# Lampara.net
KiCad netlist of a schematic drawn in EAGLE
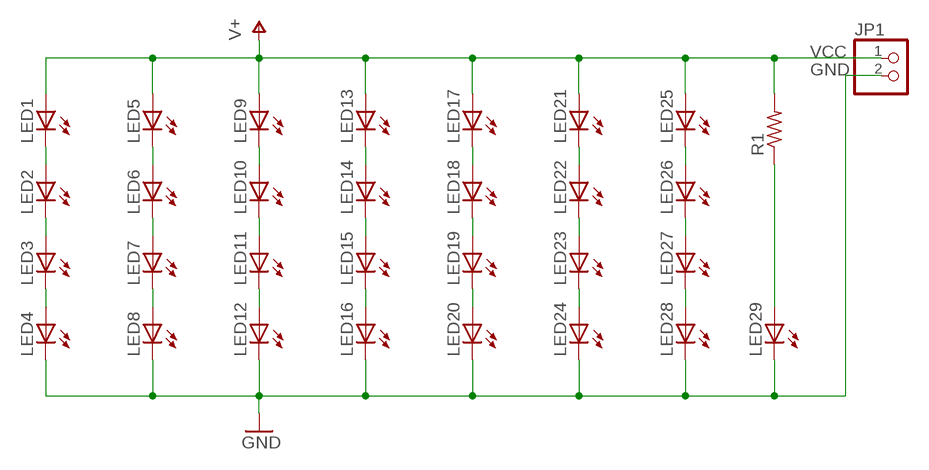
[diagram p0: schematic, sheet 1]

(export (version "E")
  (design (tool "Eeschema 10.0.6"))
  (components
    (comp (ref "JP1")
      (value "PINHD-1X2/90")
      (footprint "eagle-import:1X02_90")
      (libsource (lib "eagle-import") (part "PINHD-1X2/90"))
    )
    (comp (ref "LED1")
      (value "LED5MM")
      (footprint "eagle-import:LED5MM")
      (libsource (lib "eagle-import") (part "LED5MM"))
    )
    (comp (ref "LED2")
      (value "LED5MM")
      (footprint "eagle-import:LED5MM")
      (libsource (lib "eagle-import") (part "LED5MM"))
    )
    (comp (ref "LED3")
      (value "LED5MM")
      (footprint "eagle-import:LED5MM")
      (libsource (lib "eagle-import") (part "LED5MM"))
    )
    (comp (ref "LED4")
      (value "LED5MM")
      (footprint "eagle-import:LED5MM")
      (libsource (lib "eagle-import") (part "LED5MM"))
    )
    (comp (ref "LED5")
      (value "LED5MM")
      (footprint "eagle-import:LED5MM")
      (libsource (lib "eagle-import") (part "LED5MM"))
    )
    (comp (ref "LED6")
      (value "LED5MM")
      (footprint "eagle-import:LED5MM")
      (libsource (lib "eagle-import") (part "LED5MM"))
    )
    (comp (ref "LED7")
      (value "LED5MM")
      (footprint "eagle-import:LED5MM")
      (libsource (lib "eagle-import") (part "LED5MM"))
    )
    (comp (ref "LED8")
      (value "LED5MM")
      (footprint "eagle-import:LED5MM")
      (libsource (lib "eagle-import") (part "LED5MM"))
    )
    (comp (ref "LED9")
      (value "LED5MM")
      (footprint "eagle-import:LED5MM")
      (libsource (lib "eagle-import") (part "LED5MM"))
    )
    (comp (ref "LED10")
      (value "LED5MM")
      (footprint "eagle-import:LED5MM")
      (libsource (lib "eagle-import") (part "LED5MM"))
    )
    (comp (ref "LED11")
      (value "LED5MM")
      (footprint "eagle-import:LED5MM")
      (libsource (lib "eagle-import") (part "LED5MM"))
    )
    (comp (ref "LED12")
      (value "LED5MM")
      (footprint "eagle-import:LED5MM")
      (libsource (lib "eagle-import") (part "LED5MM"))
    )
    (comp (ref "LED13")
      (value "LED5MM")
      (footprint "eagle-import:LED5MM")
      (libsource (lib "eagle-import") (part "LED5MM"))
    )
    (comp (ref "LED14")
      (value "LED5MM")
      (footprint "eagle-import:LED5MM")
      (libsource (lib "eagle-import") (part "LED5MM"))
    )
    (comp (ref "LED15")
      (value "LED5MM")
      (footprint "eagle-import:LED5MM")
      (libsource (lib "eagle-import") (part "LED5MM"))
    )
    (comp (ref "LED16")
      (value "LED5MM")
      (footprint "eagle-import:LED5MM")
      (libsource (lib "eagle-import") (part "LED5MM"))
    )
    (comp (ref "LED17")
      (value "LED5MM")
      (footprint "eagle-import:LED5MM")
      (libsource (lib "eagle-import") (part "LED5MM"))
    )
    (comp (ref "LED18")
      (value "LED5MM")
      (footprint "eagle-import:LED5MM")
      (libsource (lib "eagle-import") (part "LED5MM"))
    )
    (comp (ref "LED19")
      (value "LED5MM")
      (footprint "eagle-import:LED5MM")
      (libsource (lib "eagle-import") (part "LED5MM"))
    )
    (comp (ref "LED20")
      (value "LED5MM")
      (footprint "eagle-import:LED5MM")
      (libsource (lib "eagle-import") (part "LED5MM"))
    )
    (comp (ref "LED21")
      (value "LED5MM")
      (footprint "eagle-import:LED5MM")
      (libsource (lib "eagle-import") (part "LED5MM"))
    )
    (comp (ref "LED22")
      (value "LED5MM")
      (footprint "eagle-import:LED5MM")
      (libsource (lib "eagle-import") (part "LED5MM"))
    )
    (comp (ref "LED23")
      (value "LED5MM")
      (footprint "eagle-import:LED5MM")
      (libsource (lib "eagle-import") (part "LED5MM"))
    )
    (comp (ref "LED24")
      (value "LED5MM")
      (footprint "eagle-import:LED5MM")
      (libsource (lib "eagle-import") (part "LED5MM"))
    )
    (comp (ref "LED25")
      (value "LED5MM")
      (footprint "eagle-import:LED5MM")
      (libsource (lib "eagle-import") (part "LED5MM"))
    )
    (comp (ref "LED26")
      (value "LED5MM")
      (footprint "eagle-import:LED5MM")
      (libsource (lib "eagle-import") (part "LED5MM"))
    )
    (comp (ref "LED27")
      (value "LED5MM")
      (footprint "eagle-import:LED5MM")
      (libsource (lib "eagle-import") (part "LED5MM"))
    )
    (comp (ref "LED28")
      (value "LED5MM")
      (footprint "eagle-import:LED5MM")
      (libsource (lib "eagle-import") (part "LED5MM"))
    )
    (comp (ref "LED29")
      (value "LED5MM")
      (footprint "eagle-import:LED5MM")
      (libsource (lib "eagle-import") (part "LED5MM"))
    )
    (comp (ref "R1")
      (value "R-US_0204/7")
      (footprint "eagle-import:0204_7")
      (libsource (lib "eagle-import") (part "R-US_0204/7"))
    )
  )
  (nets
    (net (code "1") (name "GND") (class "Default")
      (node (ref "JP1") (pin "2") (pinfunction "2_2") (pintype "passive"))
      (node (ref "LED12") (pin "K") (pinfunction "C_K") (pintype "passive"))
      (node (ref "LED16") (pin "K") (pinfunction "C_K") (pintype "passive"))
      (node (ref "LED20") (pin "K") (pinfunction "C_K") (pintype "passive"))
      (node (ref "LED24") (pin "K") (pinfunction "C_K") (pintype "passive"))
      (node (ref "LED28") (pin "K") (pinfunction "C_K") (pintype "passive"))
      (node (ref "LED29") (pin "K") (pinfunction "C_K") (pintype "passive"))
      (node (ref "LED4") (pin "K") (pinfunction "C_K") (pintype "passive"))
      (node (ref "LED8") (pin "K") (pinfunction "C_K") (pintype "passive"))
    )
    (net (code "2") (name "Net-(LED1-C)") (class "Default")
      (node (ref "LED1") (pin "K") (pinfunction "C_K") (pintype "passive"))
      (node (ref "LED2") (pin "A") (pinfunction "A_A") (pintype "passive"))
    )
    (net (code "3") (name "Net-(LED2-C)") (class "Default")
      (node (ref "LED2") (pin "K") (pinfunction "C_K") (pintype "passive"))
      (node (ref "LED3") (pin "A") (pinfunction "A_A") (pintype "passive"))
    )
    (net (code "4") (name "Net-(LED3-C)") (class "Default")
      (node (ref "LED3") (pin "K") (pinfunction "C_K") (pintype "passive"))
      (node (ref "LED4") (pin "A") (pinfunction "A_A") (pintype "passive"))
    )
    (net (code "5") (name "Net-(LED5-C)") (class "Default")
      (node (ref "LED5") (pin "K") (pinfunction "C_K") (pintype "passive"))
      (node (ref "LED6") (pin "A") (pinfunction "A_A") (pintype "passive"))
    )
    (net (code "6") (name "Net-(LED6-C)") (class "Default")
      (node (ref "LED6") (pin "K") (pinfunction "C_K") (pintype "passive"))
      (node (ref "LED7") (pin "A") (pinfunction "A_A") (pintype "passive"))
    )
    (net (code "7") (name "Net-(LED7-C)") (class "Default")
      (node (ref "LED7") (pin "K") (pinfunction "C_K") (pintype "passive"))
      (node (ref "LED8") (pin "A") (pinfunction "A_A") (pintype "passive"))
    )
    (net (code "8") (name "Net-(LED9-C)") (class "Default")
      (node (ref "LED10") (pin "A") (pinfunction "A_A") (pintype "passive"))
      (node (ref "LED9") (pin "K") (pinfunction "C_K") (pintype "passive"))
    )
    (net (code "9") (name "Net-(LED10-C)") (class "Default")
      (node (ref "LED10") (pin "K") (pinfunction "C_K") (pintype "passive"))
      (node (ref "LED11") (pin "A") (pinfunction "A_A") (pintype "passive"))
    )
    (net (code "10") (name "Net-(LED11-C)") (class "Default")
      (node (ref "LED11") (pin "K") (pinfunction "C_K") (pintype "passive"))
      (node (ref "LED12") (pin "A") (pinfunction "A_A") (pintype "passive"))
    )
    (net (code "11") (name "Net-(LED13-C)") (class "Default")
      (node (ref "LED13") (pin "K") (pinfunction "C_K") (pintype "passive"))
      (node (ref "LED14") (pin "A") (pinfunction "A_A") (pintype "passive"))
    )
    (net (code "12") (name "Net-(LED14-C)") (class "Default")
      (node (ref "LED14") (pin "K") (pinfunction "C_K") (pintype "passive"))
      (node (ref "LED15") (pin "A") (pinfunction "A_A") (pintype "passive"))
    )
    (net (code "13") (name "Net-(LED15-C)") (class "Default")
      (node (ref "LED15") (pin "K") (pinfunction "C_K") (pintype "passive"))
      (node (ref "LED16") (pin "A") (pinfunction "A_A") (pintype "passive"))
    )
    (net (code "14") (name "Net-(LED17-C)") (class "Default")
      (node (ref "LED17") (pin "K") (pinfunction "C_K") (pintype "passive"))
      (node (ref "LED18") (pin "A") (pinfunction "A_A") (pintype "passive"))
    )
    (net (code "15") (name "Net-(LED18-C)") (class "Default")
      (node (ref "LED18") (pin "K") (pinfunction "C_K") (pintype "passive"))
      (node (ref "LED19") (pin "A") (pinfunction "A_A") (pintype "passive"))
    )
    (net (code "16") (name "Net-(LED19-C)") (class "Default")
      (node (ref "LED19") (pin "K") (pinfunction "C_K") (pintype "passive"))
      (node (ref "LED20") (pin "A") (pinfunction "A_A") (pintype "passive"))
    )
    (net (code "17") (name "Net-(LED21-C)") (class "Default")
      (node (ref "LED21") (pin "K") (pinfunction "C_K") (pintype "passive"))
      (node (ref "LED22") (pin "A") (pinfunction "A_A") (pintype "passive"))
    )
    (net (code "18") (name "Net-(LED22-C)") (class "Default")
      (node (ref "LED22") (pin "K") (pinfunction "C_K") (pintype "passive"))
      (node (ref "LED23") (pin "A") (pinfunction "A_A") (pintype "passive"))
    )
    (net (code "19") (name "Net-(LED23-C)") (class "Default")
      (node (ref "LED23") (pin "K") (pinfunction "C_K") (pintype "passive"))
      (node (ref "LED24") (pin "A") (pinfunction "A_A") (pintype "passive"))
    )
    (net (code "20") (name "Net-(LED25-C)") (class "Default")
      (node (ref "LED25") (pin "K") (pinfunction "C_K") (pintype "passive"))
      (node (ref "LED26") (pin "A") (pinfunction "A_A") (pintype "passive"))
    )
    (net (code "21") (name "Net-(LED26-C)") (class "Default")
      (node (ref "LED26") (pin "K") (pinfunction "C_K") (pintype "passive"))
      (node (ref "LED27") (pin "A") (pinfunction "A_A") (pintype "passive"))
    )
    (net (code "22") (name "Net-(LED27-C)") (class "Default")
      (node (ref "LED27") (pin "K") (pinfunction "C_K") (pintype "passive"))
      (node (ref "LED28") (pin "A") (pinfunction "A_A") (pintype "passive"))
    )
    (net (code "23") (name "Net-(LED29-PadA)") (class "Default")
      (node (ref "LED29") (pin "A") (pinfunction "A_A") (pintype "passive"))
      (node (ref "R1") (pin "1") (pinfunction "1_1") (pintype "passive"))
    )
    (net (code "24") (name "V+") (class "Default")
      (node (ref "JP1") (pin "1") (pinfunction "1_1") (pintype "passive"))
      (node (ref "LED1") (pin "A") (pinfunction "A_A") (pintype "passive"))
      (node (ref "LED13") (pin "A") (pinfunction "A_A") (pintype "passive"))
      (node (ref "LED17") (pin "A") (pinfunction "A_A") (pintype "passive"))
      (node (ref "LED21") (pin "A") (pinfunction "A_A") (pintype "passive"))
      (node (ref "LED25") (pin "A") (pinfunction "A_A") (pintype "passive"))
      (node (ref "LED5") (pin "A") (pinfunction "A_A") (pintype "passive"))
      (node (ref "LED9") (pin "A") (pinfunction "A_A") (pintype "passive"))
      (node (ref "R1") (pin "2") (pinfunction "2_2") (pintype "passive"))
    )
  )
)
